# Dist_2_0.net
KiCad netlist of a schematic drawn in EAGLE
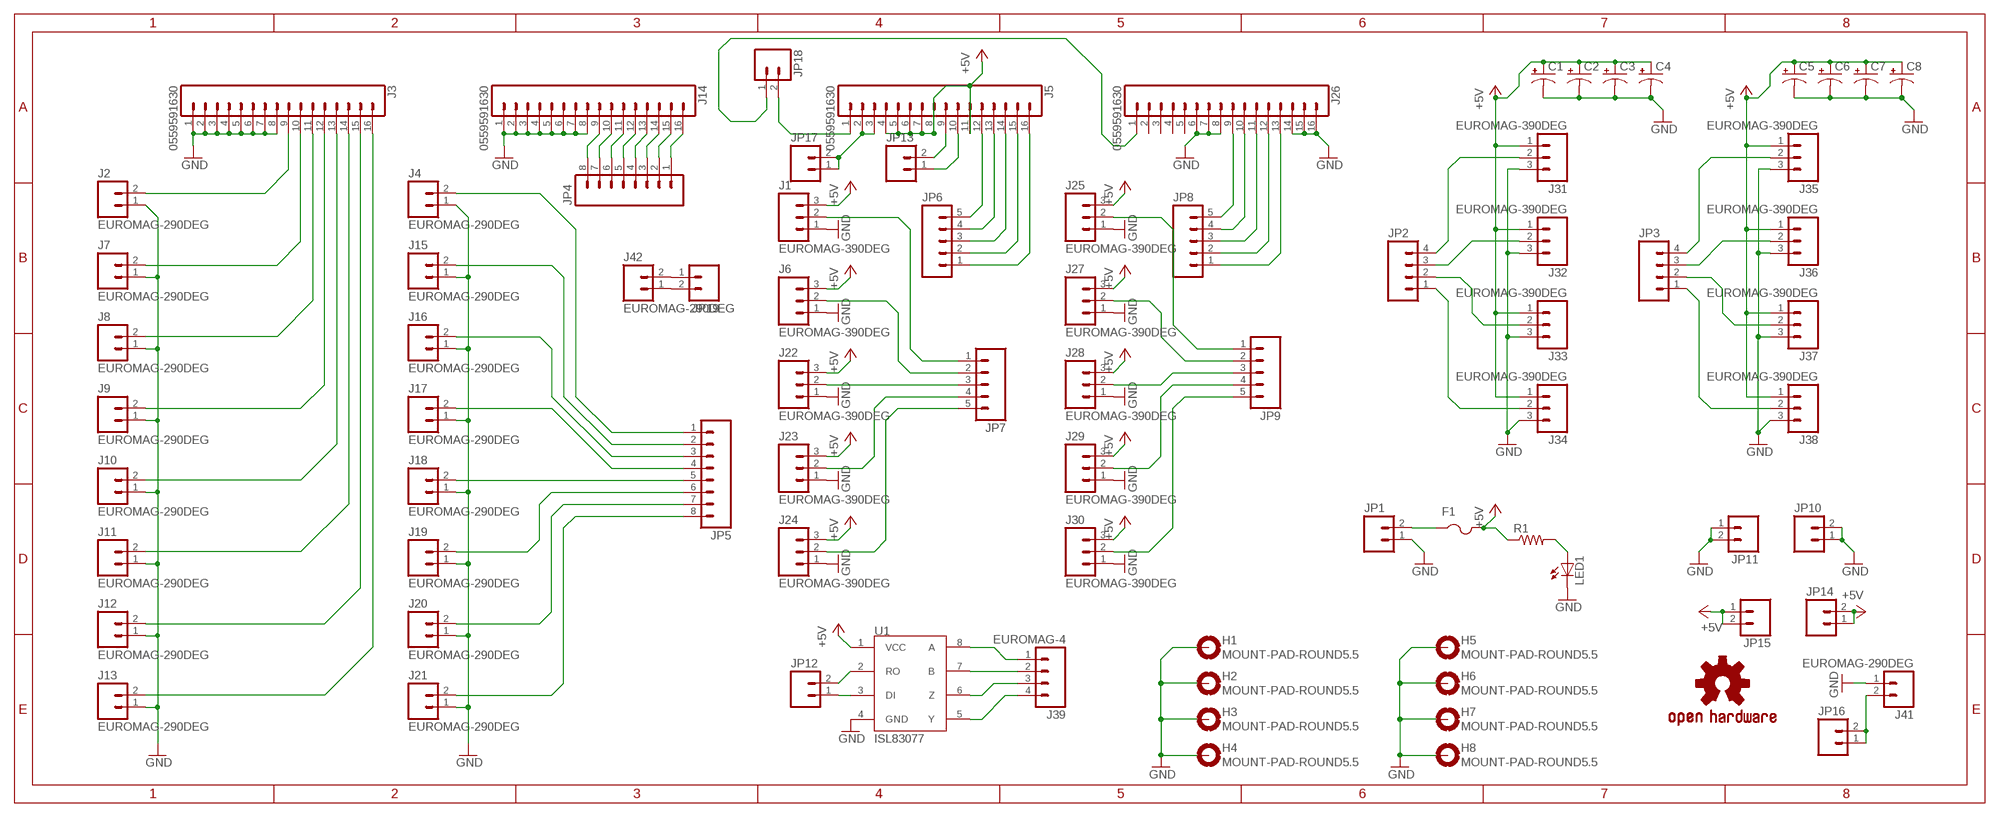
[diagram p0: schematic, sheet 1]

(export (version "E")
  (design (tool "Eeschema 10.0.6"))
  (components
    (comp (ref "C1")
      (value "CAP_POL3528")
      (footprint "eagle-import:EIA3528")
      (libsource (lib "eagle-import") (part "CAP_POL3528"))
    )
    (comp (ref "C2")
      (value "CAP_POL3528")
      (footprint "eagle-import:EIA3528")
      (libsource (lib "eagle-import") (part "CAP_POL3528"))
    )
    (comp (ref "C3")
      (value "CAP_POL3528")
      (footprint "eagle-import:EIA3528")
      (libsource (lib "eagle-import") (part "CAP_POL3528"))
    )
    (comp (ref "C4")
      (value "CAP_POL3528")
      (footprint "eagle-import:EIA3528")
      (libsource (lib "eagle-import") (part "CAP_POL3528"))
    )
    (comp (ref "C5")
      (value "CAP_POL3528")
      (footprint "eagle-import:EIA3528")
      (libsource (lib "eagle-import") (part "CAP_POL3528"))
    )
    (comp (ref "C6")
      (value "CAP_POL3528")
      (footprint "eagle-import:EIA3528")
      (libsource (lib "eagle-import") (part "CAP_POL3528"))
    )
    (comp (ref "C7")
      (value "CAP_POL3528")
      (footprint "eagle-import:EIA3528")
      (libsource (lib "eagle-import") (part "CAP_POL3528"))
    )
    (comp (ref "C8")
      (value "CAP_POL3528")
      (footprint "eagle-import:EIA3528")
      (libsource (lib "eagle-import") (part "CAP_POL3528"))
    )
    (comp (ref "F1")
      (value "PTCFUSE-1812")
      (footprint "eagle-import:1812")
      (libsource (lib "eagle-import") (part "PTCFUSE-1812"))
    )
    (comp (ref "H1")
      (value "MOUNT-PAD-ROUND5.5")
      (footprint "eagle-import:5,5-PAD")
      (libsource (lib "eagle-import") (part "MOUNT-PAD-ROUND5.5"))
    )
    (comp (ref "H2")
      (value "MOUNT-PAD-ROUND5.5")
      (footprint "eagle-import:5,5-PAD")
      (libsource (lib "eagle-import") (part "MOUNT-PAD-ROUND5.5"))
    )
    (comp (ref "H3")
      (value "MOUNT-PAD-ROUND5.5")
      (footprint "eagle-import:5,5-PAD")
      (libsource (lib "eagle-import") (part "MOUNT-PAD-ROUND5.5"))
    )
    (comp (ref "H4")
      (value "MOUNT-PAD-ROUND5.5")
      (footprint "eagle-import:5,5-PAD")
      (libsource (lib "eagle-import") (part "MOUNT-PAD-ROUND5.5"))
    )
    (comp (ref "H5")
      (value "MOUNT-PAD-ROUND5.5")
      (footprint "eagle-import:5,5-PAD")
      (libsource (lib "eagle-import") (part "MOUNT-PAD-ROUND5.5"))
    )
    (comp (ref "H6")
      (value "MOUNT-PAD-ROUND5.5")
      (footprint "eagle-import:5,5-PAD")
      (libsource (lib "eagle-import") (part "MOUNT-PAD-ROUND5.5"))
    )
    (comp (ref "H7")
      (value "MOUNT-PAD-ROUND5.5")
      (footprint "eagle-import:5,5-PAD")
      (libsource (lib "eagle-import") (part "MOUNT-PAD-ROUND5.5"))
    )
    (comp (ref "H8")
      (value "MOUNT-PAD-ROUND5.5")
      (footprint "eagle-import:5,5-PAD")
      (libsource (lib "eagle-import") (part "MOUNT-PAD-ROUND5.5"))
    )
    (comp (ref "J1")
      (value "EUROMAG-390DEG")
      (footprint "eagle-import:M3")
      (libsource (lib "eagle-import") (part "EUROMAG-390DEG"))
    )
    (comp (ref "J2")
      (value "EUROMAG-290DEG")
      (footprint "eagle-import:M2")
      (libsource (lib "eagle-import") (part "EUROMAG-290DEG"))
    )
    (comp (ref "J3")
      (value "0559591630")
      (footprint "eagle-import:0559591630")
      (libsource (lib "eagle-import") (part "0559591630"))
    )
    (comp (ref "J4")
      (value "EUROMAG-290DEG")
      (footprint "eagle-import:M2")
      (libsource (lib "eagle-import") (part "EUROMAG-290DEG"))
    )
    (comp (ref "J5")
      (value "0559591630")
      (footprint "eagle-import:0559591630")
      (libsource (lib "eagle-import") (part "0559591630"))
    )
    (comp (ref "J6")
      (value "EUROMAG-390DEG")
      (footprint "eagle-import:M3")
      (libsource (lib "eagle-import") (part "EUROMAG-390DEG"))
    )
    (comp (ref "J7")
      (value "EUROMAG-290DEG")
      (footprint "eagle-import:M2")
      (libsource (lib "eagle-import") (part "EUROMAG-290DEG"))
    )
    (comp (ref "J8")
      (value "EUROMAG-290DEG")
      (footprint "eagle-import:M2")
      (libsource (lib "eagle-import") (part "EUROMAG-290DEG"))
    )
    (comp (ref "J9")
      (value "EUROMAG-290DEG")
      (footprint "eagle-import:M2")
      (libsource (lib "eagle-import") (part "EUROMAG-290DEG"))
    )
    (comp (ref "J10")
      (value "EUROMAG-290DEG")
      (footprint "eagle-import:M2")
      (libsource (lib "eagle-import") (part "EUROMAG-290DEG"))
    )
    (comp (ref "J11")
      (value "EUROMAG-290DEG")
      (footprint "eagle-import:M2")
      (libsource (lib "eagle-import") (part "EUROMAG-290DEG"))
    )
    (comp (ref "J12")
      (value "EUROMAG-290DEG")
      (footprint "eagle-import:M2")
      (libsource (lib "eagle-import") (part "EUROMAG-290DEG"))
    )
    (comp (ref "J13")
      (value "EUROMAG-290DEG")
      (footprint "eagle-import:M2")
      (libsource (lib "eagle-import") (part "EUROMAG-290DEG"))
    )
    (comp (ref "J14")
      (value "0559591630")
      (footprint "eagle-import:0559591630")
      (libsource (lib "eagle-import") (part "0559591630"))
    )
    (comp (ref "J15")
      (value "EUROMAG-290DEG")
      (footprint "eagle-import:M2")
      (libsource (lib "eagle-import") (part "EUROMAG-290DEG"))
    )
    (comp (ref "J16")
      (value "EUROMAG-290DEG")
      (footprint "eagle-import:M2")
      (libsource (lib "eagle-import") (part "EUROMAG-290DEG"))
    )
    (comp (ref "J17")
      (value "EUROMAG-290DEG")
      (footprint "eagle-import:M2")
      (libsource (lib "eagle-import") (part "EUROMAG-290DEG"))
    )
    (comp (ref "J18")
      (value "EUROMAG-290DEG")
      (footprint "eagle-import:M2")
      (libsource (lib "eagle-import") (part "EUROMAG-290DEG"))
    )
    (comp (ref "J19")
      (value "EUROMAG-290DEG")
      (footprint "eagle-import:M2")
      (libsource (lib "eagle-import") (part "EUROMAG-290DEG"))
    )
    (comp (ref "J20")
      (value "EUROMAG-290DEG")
      (footprint "eagle-import:M2")
      (libsource (lib "eagle-import") (part "EUROMAG-290DEG"))
    )
    (comp (ref "J21")
      (value "EUROMAG-290DEG")
      (footprint "eagle-import:M2")
      (libsource (lib "eagle-import") (part "EUROMAG-290DEG"))
    )
    (comp (ref "J22")
      (value "EUROMAG-390DEG")
      (footprint "eagle-import:M3")
      (libsource (lib "eagle-import") (part "EUROMAG-390DEG"))
    )
    (comp (ref "J23")
      (value "EUROMAG-390DEG")
      (footprint "eagle-import:M3")
      (libsource (lib "eagle-import") (part "EUROMAG-390DEG"))
    )
    (comp (ref "J24")
      (value "EUROMAG-390DEG")
      (footprint "eagle-import:M3")
      (libsource (lib "eagle-import") (part "EUROMAG-390DEG"))
    )
    (comp (ref "J25")
      (value "EUROMAG-390DEG")
      (footprint "eagle-import:M3")
      (libsource (lib "eagle-import") (part "EUROMAG-390DEG"))
    )
    (comp (ref "J26")
      (value "0559591630")
      (footprint "eagle-import:0559591630")
      (libsource (lib "eagle-import") (part "0559591630"))
    )
    (comp (ref "J27")
      (value "EUROMAG-390DEG")
      (footprint "eagle-import:M3")
      (libsource (lib "eagle-import") (part "EUROMAG-390DEG"))
    )
    (comp (ref "J28")
      (value "EUROMAG-390DEG")
      (footprint "eagle-import:M3")
      (libsource (lib "eagle-import") (part "EUROMAG-390DEG"))
    )
    (comp (ref "J29")
      (value "EUROMAG-390DEG")
      (footprint "eagle-import:M3")
      (libsource (lib "eagle-import") (part "EUROMAG-390DEG"))
    )
    (comp (ref "J30")
      (value "EUROMAG-390DEG")
      (footprint "eagle-import:M3")
      (libsource (lib "eagle-import") (part "EUROMAG-390DEG"))
    )
    (comp (ref "J31")
      (value "EUROMAG-390DEG")
      (footprint "eagle-import:M3")
      (libsource (lib "eagle-import") (part "EUROMAG-390DEG"))
    )
    (comp (ref "J32")
      (value "EUROMAG-390DEG")
      (footprint "eagle-import:M3")
      (libsource (lib "eagle-import") (part "EUROMAG-390DEG"))
    )
    (comp (ref "J33")
      (value "EUROMAG-390DEG")
      (footprint "eagle-import:M3")
      (libsource (lib "eagle-import") (part "EUROMAG-390DEG"))
    )
    (comp (ref "J34")
      (value "EUROMAG-390DEG")
      (footprint "eagle-import:M3")
      (libsource (lib "eagle-import") (part "EUROMAG-390DEG"))
    )
    (comp (ref "J35")
      (value "EUROMAG-390DEG")
      (footprint "eagle-import:M3")
      (libsource (lib "eagle-import") (part "EUROMAG-390DEG"))
    )
    (comp (ref "J36")
      (value "EUROMAG-390DEG")
      (footprint "eagle-import:M3")
      (libsource (lib "eagle-import") (part "EUROMAG-390DEG"))
    )
    (comp (ref "J37")
      (value "EUROMAG-390DEG")
      (footprint "eagle-import:M3")
      (libsource (lib "eagle-import") (part "EUROMAG-390DEG"))
    )
    (comp (ref "J38")
      (value "EUROMAG-390DEG")
      (footprint "eagle-import:M3")
      (libsource (lib "eagle-import") (part "EUROMAG-390DEG"))
    )
    (comp (ref "J39")
      (value "EUROMAG-4")
      (footprint "eagle-import:M4")
      (libsource (lib "eagle-import") (part "EUROMAG-4"))
    )
    (comp (ref "J41")
      (value "EUROMAG-290DEG")
      (footprint "eagle-import:M2")
      (libsource (lib "eagle-import") (part "EUROMAG-290DEG"))
    )
    (comp (ref "J42")
      (value "EUROMAG-290DEG")
      (footprint "eagle-import:M2")
      (libsource (lib "eagle-import") (part "EUROMAG-290DEG"))
    )
    (comp (ref "JP1")
      (value "M02POLAR_LOCK")
      (footprint "eagle-import:MOLEX-1X2_LOCK")
      (libsource (lib "eagle-import") (part "M02POLAR_LOCK"))
    )
    (comp (ref "JP2")
      (value "M04POLAR_LOCK")
      (footprint "eagle-import:MOLEX-1X4_LOCK")
      (libsource (lib "eagle-import") (part "M04POLAR_LOCK"))
    )
    (comp (ref "JP3")
      (value "M04POLAR_LOCK")
      (footprint "eagle-import:MOLEX-1X4_LOCK")
      (libsource (lib "eagle-import") (part "M04POLAR_LOCK"))
    )
    (comp (ref "JP4")
      (value "M08LOCK_LONGPADS")
      (footprint "eagle-import:1X08_LOCK_LONGPADS")
      (libsource (lib "eagle-import") (part "M08LOCK_LONGPADS"))
    )
    (comp (ref "JP5")
      (value "M08LOCK_LONGPADS")
      (footprint "eagle-import:1X08_LOCK_LONGPADS")
      (libsource (lib "eagle-import") (part "M08LOCK_LONGPADS"))
    )
    (comp (ref "JP6")
      (value "M05LOCK_LONGPADS")
      (footprint "eagle-import:1X05_LOCK_LONGPADS")
      (libsource (lib "eagle-import") (part "M05LOCK_LONGPADS"))
    )
    (comp (ref "JP7")
      (value "M05LOCK_LONGPADS")
      (footprint "eagle-import:1X05_LOCK_LONGPADS")
      (libsource (lib "eagle-import") (part "M05LOCK_LONGPADS"))
    )
    (comp (ref "JP8")
      (value "M05LOCK_LONGPADS")
      (footprint "eagle-import:1X05_LOCK_LONGPADS")
      (libsource (lib "eagle-import") (part "M05LOCK_LONGPADS"))
    )
    (comp (ref "JP9")
      (value "M05LOCK_LONGPADS")
      (footprint "eagle-import:1X05_LOCK_LONGPADS")
      (libsource (lib "eagle-import") (part "M05LOCK_LONGPADS"))
    )
    (comp (ref "JP10")
      (value "M02PTH")
      (footprint "eagle-import:1X02")
      (libsource (lib "eagle-import") (part "SparkFun-Connectors_M02PTH"))
    )
    (comp (ref "JP11")
      (value "M02PTH")
      (footprint "eagle-import:1X02")
      (libsource (lib "eagle-import") (part "SparkFun-Connectors_M02PTH"))
    )
    (comp (ref "JP12")
      (value "M02PTH")
      (footprint "eagle-import:1X02")
      (libsource (lib "eagle-import") (part "SparkFun-Connectors_M02PTH"))
    )
    (comp (ref "JP13")
      (value "M02PTH")
      (footprint "eagle-import:1X02")
      (libsource (lib "eagle-import") (part "SparkFun-Connectors_M02PTH"))
    )
    (comp (ref "JP14")
      (value "M02PTH")
      (footprint "eagle-import:1X02")
      (libsource (lib "eagle-import") (part "SparkFun-Connectors_M02PTH"))
    )
    (comp (ref "JP15")
      (value "M02PTH")
      (footprint "eagle-import:1X02")
      (libsource (lib "eagle-import") (part "SparkFun-Connectors_M02PTH"))
    )
    (comp (ref "JP16")
      (value "M02PTH")
      (footprint "eagle-import:1X02")
      (libsource (lib "eagle-import") (part "SparkFun-Connectors_M02PTH"))
    )
    (comp (ref "JP17")
      (value "M02PTH")
      (footprint "eagle-import:1X02")
      (libsource (lib "eagle-import") (part "SparkFun-Connectors_M02PTH"))
    )
    (comp (ref "JP18")
      (value "M02PTH")
      (footprint "eagle-import:1X02")
      (libsource (lib "eagle-import") (part "SparkFun-Connectors_M02PTH"))
    )
    (comp (ref "JP19")
      (value "M02PTH")
      (footprint "eagle-import:1X02")
      (libsource (lib "eagle-import") (part "SparkFun-Connectors_M02PTH"))
    )
    (comp (ref "LED1")
      (value "LEDCHIPLED_0805")
      (footprint "eagle-import:CHIPLED_0805")
      (libsource (lib "eagle-import") (part "LEDCHIPLED_0805"))
    )
    (comp (ref "R1")
      (value "R-US_R0805")
      (footprint "eagle-import:R0805")
      (libsource (lib "eagle-import") (part "R-US_R0805"))
    )
    (comp (ref "U$1")
      (value "OSHW-LOGOL")
      (footprint "eagle-import:OSHW-LOGO-L")
      (libsource (lib "eagle-import") (part "OSHW-LOGOL"))
    )
    (comp (ref "U1")
      (value "ISL83077")
      (footprint "eagle-import:SO08")
      (libsource (lib "eagle-import") (part "ISL83077"))
    )
  )
  (nets
    (net (code "1") (name "+5V") (class "Default")
      (node (ref "C1") (pin "A") (pinfunction "+_A") (pintype "passive"))
      (node (ref "C2") (pin "A") (pinfunction "+_A") (pintype "passive"))
      (node (ref "C3") (pin "A") (pinfunction "+_A") (pintype "passive"))
      (node (ref "C4") (pin "A") (pinfunction "+_A") (pintype "passive"))
      (node (ref "C5") (pin "A") (pinfunction "+_A") (pintype "passive"))
      (node (ref "C6") (pin "A") (pinfunction "+_A") (pintype "passive"))
      (node (ref "C7") (pin "A") (pinfunction "+_A") (pintype "passive"))
      (node (ref "C8") (pin "A") (pinfunction "+_A") (pintype "passive"))
      (node (ref "F1") (pin "2") (pinfunction "2_2") (pintype "passive"))
      (node (ref "J1") (pin "3") (pinfunction "3_3") (pintype "passive"))
      (node (ref "J22") (pin "3") (pinfunction "3_3") (pintype "passive"))
      (node (ref "J23") (pin "3") (pinfunction "3_3") (pintype "passive"))
      (node (ref "J24") (pin "3") (pinfunction "3_3") (pintype "passive"))
      (node (ref "J25") (pin "3") (pinfunction "3_3") (pintype "passive"))
      (node (ref "J27") (pin "3") (pinfunction "3_3") (pintype "passive"))
      (node (ref "J28") (pin "3") (pinfunction "3_3") (pintype "passive"))
      (node (ref "J29") (pin "3") (pinfunction "3_3") (pintype "passive"))
      (node (ref "J30") (pin "3") (pinfunction "3_3") (pintype "passive"))
      (node (ref "J31") (pin "1") (pinfunction "1_1") (pintype "passive"))
      (node (ref "J32") (pin "1") (pinfunction "1_1") (pintype "passive"))
      (node (ref "J33") (pin "1") (pinfunction "1_1") (pintype "passive"))
      (node (ref "J34") (pin "1") (pinfunction "1_1") (pintype "passive"))
      (node (ref "J35") (pin "1") (pinfunction "1_1") (pintype "passive"))
      (node (ref "J36") (pin "1") (pinfunction "1_1") (pintype "passive"))
      (node (ref "J37") (pin "1") (pinfunction "1_1") (pintype "passive"))
      (node (ref "J38") (pin "1") (pinfunction "1_1") (pintype "passive"))
      (node (ref "J5") (pin "11") (pinfunction "11_11") (pintype "passive"))
      (node (ref "J5") (pin "4") (pinfunction "4_4") (pintype "passive"))
      (node (ref "J5") (pin "5") (pinfunction "5_5") (pintype "passive"))
      (node (ref "J5") (pin "6") (pinfunction "6_6") (pintype "passive"))
      (node (ref "J5") (pin "7") (pinfunction "7_7") (pintype "passive"))
      (node (ref "J5") (pin "8") (pinfunction "8_8") (pintype "passive"))
      (node (ref "J6") (pin "3") (pinfunction "3_3") (pintype "passive"))
      (node (ref "JP14") (pin "1") (pinfunction "1_1") (pintype "passive"))
      (node (ref "JP14") (pin "2") (pinfunction "2_2") (pintype "passive"))
      (node (ref "JP15") (pin "1") (pinfunction "1_1") (pintype "passive"))
      (node (ref "JP15") (pin "2") (pinfunction "2_2") (pintype "passive"))
      (node (ref "R1") (pin "1") (pinfunction "1_1") (pintype "passive"))
      (node (ref "U1") (pin "1") (pinfunction "VCC_1") (pintype "bidirectional"))
    )
    (net (code "2") (name "GND") (class "Default")
      (node (ref "C1") (pin "C") (pinfunction "-_C") (pintype "passive"))
      (node (ref "C2") (pin "C") (pinfunction "-_C") (pintype "passive"))
      (node (ref "C3") (pin "C") (pinfunction "-_C") (pintype "passive"))
      (node (ref "C4") (pin "C") (pinfunction "-_C") (pintype "passive"))
      (node (ref "C5") (pin "C") (pinfunction "-_C") (pintype "passive"))
      (node (ref "C6") (pin "C") (pinfunction "-_C") (pintype "passive"))
      (node (ref "C7") (pin "C") (pinfunction "-_C") (pintype "passive"))
      (node (ref "C8") (pin "C") (pinfunction "-_C") (pintype "passive"))
      (node (ref "H1") (pin "B5,5") (pinfunction "MOUNT_B5,5") (pintype "passive"))
      (node (ref "H2") (pin "B5,5") (pinfunction "MOUNT_B5,5") (pintype "passive"))
      (node (ref "H3") (pin "B5,5") (pinfunction "MOUNT_B5,5") (pintype "passive"))
      (node (ref "H4") (pin "B5,5") (pinfunction "MOUNT_B5,5") (pintype "passive"))
      (node (ref "H5") (pin "B5,5") (pinfunction "MOUNT_B5,5") (pintype "passive"))
      (node (ref "H6") (pin "B5,5") (pinfunction "MOUNT_B5,5") (pintype "passive"))
      (node (ref "H7") (pin "B5,5") (pinfunction "MOUNT_B5,5") (pintype "passive"))
      (node (ref "H8") (pin "B5,5") (pinfunction "MOUNT_B5,5") (pintype "passive"))
      (node (ref "J1") (pin "1") (pinfunction "1_1") (pintype "passive"))
      (node (ref "J10") (pin "1") (pinfunction "1_1") (pintype "passive"))
      (node (ref "J11") (pin "1") (pinfunction "1_1") (pintype "passive"))
      (node (ref "J12") (pin "1") (pinfunction "1_1") (pintype "passive"))
      (node (ref "J13") (pin "1") (pinfunction "1_1") (pintype "passive"))
      (node (ref "J14") (pin "1") (pinfunction "1_1") (pintype "passive"))
      (node (ref "J14") (pin "2") (pinfunction "2_2") (pintype "passive"))
      (node (ref "J14") (pin "3") (pinfunction "3_3") (pintype "passive"))
      (node (ref "J14") (pin "4") (pinfunction "4_4") (pintype "passive"))
      (node (ref "J14") (pin "5") (pinfunction "5_5") (pintype "passive"))
      (node (ref "J14") (pin "6") (pinfunction "6_6") (pintype "passive"))
      (node (ref "J14") (pin "7") (pinfunction "7_7") (pintype "passive"))
      (node (ref "J14") (pin "8") (pinfunction "8_8") (pintype "passive"))
      (node (ref "J15") (pin "1") (pinfunction "1_1") (pintype "passive"))
      (node (ref "J16") (pin "1") (pinfunction "1_1") (pintype "passive"))
      (node (ref "J17") (pin "1") (pinfunction "1_1") (pintype "passive"))
      (node (ref "J18") (pin "1") (pinfunction "1_1") (pintype "passive"))
      (node (ref "J19") (pin "1") (pinfunction "1_1") (pintype "passive"))
      (node (ref "J2") (pin "1") (pinfunction "1_1") (pintype "passive"))
      (node (ref "J20") (pin "1") (pinfunction "1_1") (pintype "passive"))
      (node (ref "J21") (pin "1") (pinfunction "1_1") (pintype "passive"))
      (node (ref "J22") (pin "1") (pinfunction "1_1") (pintype "passive"))
      (node (ref "J23") (pin "1") (pinfunction "1_1") (pintype "passive"))
      (node (ref "J24") (pin "1") (pinfunction "1_1") (pintype "passive"))
      (node (ref "J25") (pin "1") (pinfunction "1_1") (pintype "passive"))
      (node (ref "J26") (pin "14") (pinfunction "14_14") (pintype "passive"))
      (node (ref "J26") (pin "15") (pinfunction "15_15") (pintype "passive"))
      (node (ref "J26") (pin "16") (pinfunction "16_16") (pintype "passive"))
      (node (ref "J26") (pin "6") (pinfunction "6_6") (pintype "passive"))
      (node (ref "J26") (pin "7") (pinfunction "7_7") (pintype "passive"))
      (node (ref "J26") (pin "8") (pinfunction "8_8") (pintype "passive"))
      (node (ref "J27") (pin "1") (pinfunction "1_1") (pintype "passive"))
      (node (ref "J28") (pin "1") (pinfunction "1_1") (pintype "passive"))
      (node (ref "J29") (pin "1") (pinfunction "1_1") (pintype "passive"))
      (node (ref "J3") (pin "1") (pinfunction "1_1") (pintype "passive"))
      (node (ref "J3") (pin "2") (pinfunction "2_2") (pintype "passive"))
      (node (ref "J3") (pin "3") (pinfunction "3_3") (pintype "passive"))
      (node (ref "J3") (pin "4") (pinfunction "4_4") (pintype "passive"))
      (node (ref "J3") (pin "5") (pinfunction "5_5") (pintype "passive"))
      (node (ref "J3") (pin "6") (pinfunction "6_6") (pintype "passive"))
      (node (ref "J3") (pin "7") (pinfunction "7_7") (pintype "passive"))
      (node (ref "J3") (pin "8") (pinfunction "8_8") (pintype "passive"))
      (node (ref "J30") (pin "1") (pinfunction "1_1") (pintype "passive"))
      (node (ref "J31") (pin "3") (pinfunction "3_3") (pintype "passive"))
      (node (ref "J32") (pin "3") (pinfunction "3_3") (pintype "passive"))
      (node (ref "J33") (pin "3") (pinfunction "3_3") (pintype "passive"))
      (node (ref "J34") (pin "3") (pinfunction "3_3") (pintype "passive"))
      (node (ref "J35") (pin "3") (pinfunction "3_3") (pintype "passive"))
      (node (ref "J36") (pin "3") (pinfunction "3_3") (pintype "passive"))
      (node (ref "J37") (pin "3") (pinfunction "3_3") (pintype "passive"))
      (node (ref "J38") (pin "3") (pinfunction "3_3") (pintype "passive"))
      (node (ref "J4") (pin "1") (pinfunction "1_1") (pintype "passive"))
      (node (ref "J41") (pin "1") (pinfunction "1_1") (pintype "passive"))
      (node (ref "J6") (pin "1") (pinfunction "1_1") (pintype "passive"))
      (node (ref "J7") (pin "1") (pinfunction "1_1") (pintype "passive"))
      (node (ref "J8") (pin "1") (pinfunction "1_1") (pintype "passive"))
      (node (ref "J9") (pin "1") (pinfunction "1_1") (pintype "passive"))
      (node (ref "JP1") (pin "1") (pinfunction "1_1") (pintype "passive"))
      (node (ref "JP10") (pin "1") (pinfunction "1_1") (pintype "passive"))
      (node (ref "JP10") (pin "2") (pinfunction "2_2") (pintype "passive"))
      (node (ref "JP11") (pin "1") (pinfunction "1_1") (pintype "passive"))
      (node (ref "JP11") (pin "2") (pinfunction "2_2") (pintype "passive"))
      (node (ref "LED1") (pin "C") (pinfunction "C_C") (pintype "passive"))
      (node (ref "U1") (pin "4") (pinfunction "GND_4") (pintype "bidirectional"))
    )
    (net (code "3") (name "Net-(F1-Pad1)") (class "Default")
      (node (ref "F1") (pin "1") (pinfunction "1_1") (pintype "passive"))
      (node (ref "JP1") (pin "2") (pinfunction "2_2") (pintype "passive"))
    )
    (net (code "4") (name "Net-(J1-Pad2)") (class "Default")
      (node (ref "J1") (pin "2") (pinfunction "2_2") (pintype "passive"))
      (node (ref "JP7") (pin "1") (pinfunction "1_1") (pintype "passive"))
    )
    (net (code "5") (name "Net-(J2-Pad2)") (class "Default")
      (node (ref "J2") (pin "2") (pinfunction "2_2") (pintype "passive"))
      (node (ref "J3") (pin "9") (pinfunction "9_9") (pintype "passive"))
    )
    (net (code "6") (name "Net-(J3-Pad10)") (class "Default")
      (node (ref "J3") (pin "10") (pinfunction "10_10") (pintype "passive"))
      (node (ref "J7") (pin "2") (pinfunction "2_2") (pintype "passive"))
    )
    (net (code "7") (name "Net-(J3-Pad11)") (class "Default")
      (node (ref "J3") (pin "11") (pinfunction "11_11") (pintype "passive"))
      (node (ref "J8") (pin "2") (pinfunction "2_2") (pintype "passive"))
    )
    (net (code "8") (name "Net-(J3-Pad12)") (class "Default")
      (node (ref "J3") (pin "12") (pinfunction "12_12") (pintype "passive"))
      (node (ref "J9") (pin "2") (pinfunction "2_2") (pintype "passive"))
    )
    (net (code "9") (name "Net-(J4-Pad2)") (class "Default")
      (node (ref "J4") (pin "2") (pinfunction "2_2") (pintype "passive"))
      (node (ref "JP5") (pin "1") (pinfunction "1_1") (pintype "passive"))
    )
    (net (code "10") (name "Net-(J5-Pad1)") (class "Default")
      (node (ref "J5") (pin "1") (pinfunction "1_1") (pintype "passive"))
      (node (ref "JP18") (pin "2") (pinfunction "2_2") (pintype "passive"))
    )
    (net (code "11") (name "Net-(J5-Pad2)") (class "Default")
      (node (ref "J5") (pin "2") (pinfunction "2_2") (pintype "passive"))
      (node (ref "J5") (pin "3") (pinfunction "3_3") (pintype "passive"))
      (node (ref "JP17") (pin "1") (pinfunction "1_1") (pintype "passive"))
      (node (ref "JP17") (pin "2") (pinfunction "2_2") (pintype "passive"))
    )
    (net (code "12") (name "Net-(J5-Pad9)") (class "Default")
      (node (ref "J5") (pin "9") (pinfunction "9_9") (pintype "passive"))
      (node (ref "JP13") (pin "2") (pinfunction "2_2") (pintype "passive"))
    )
    (net (code "13") (name "Net-(J5-Pad10)") (class "Default")
      (node (ref "J5") (pin "10") (pinfunction "10_10") (pintype "passive"))
      (node (ref "JP13") (pin "1") (pinfunction "1_1") (pintype "passive"))
    )
    (net (code "14") (name "Net-(J5-Pad12)") (class "Default")
      (node (ref "J5") (pin "12") (pinfunction "12_12") (pintype "passive"))
      (node (ref "JP6") (pin "5") (pinfunction "5_5") (pintype "passive"))
    )
    (net (code "15") (name "Net-(J5-Pad13)") (class "Default")
      (node (ref "J5") (pin "13") (pinfunction "13_13") (pintype "passive"))
      (node (ref "JP6") (pin "4") (pinfunction "4_4") (pintype "passive"))
    )
    (net (code "16") (name "Net-(J5-Pad14)") (class "Default")
      (node (ref "J5") (pin "14") (pinfunction "14_14") (pintype "passive"))
      (node (ref "JP6") (pin "3") (pinfunction "3_3") (pintype "passive"))
    )
    (net (code "17") (name "Net-(J5-Pad15)") (class "Default")
      (node (ref "J5") (pin "15") (pinfunction "15_15") (pintype "passive"))
      (node (ref "JP6") (pin "2") (pinfunction "2_2") (pintype "passive"))
    )
    (net (code "18") (name "Net-(J5-Pad16)") (class "Default")
      (node (ref "J5") (pin "16") (pinfunction "16_16") (pintype "passive"))
      (node (ref "JP6") (pin "1") (pinfunction "1_1") (pintype "passive"))
    )
    (net (code "19") (name "Net-(J6-Pad2)") (class "Default")
      (node (ref "J6") (pin "2") (pinfunction "2_2") (pintype "passive"))
      (node (ref "JP7") (pin "2") (pinfunction "2_2") (pintype "passive"))
    )
    (net (code "20") (name "Net-(J10-Pad2)") (class "Default")
      (node (ref "J10") (pin "2") (pinfunction "2_2") (pintype "passive"))
      (node (ref "J3") (pin "13") (pinfunction "13_13") (pintype "passive"))
    )
    (net (code "21") (name "Net-(J11-Pad2)") (class "Default")
      (node (ref "J11") (pin "2") (pinfunction "2_2") (pintype "passive"))
      (node (ref "J3") (pin "14") (pinfunction "14_14") (pintype "passive"))
    )
    (net (code "22") (name "Net-(J12-Pad2)") (class "Default")
      (node (ref "J12") (pin "2") (pinfunction "2_2") (pintype "passive"))
      (node (ref "J3") (pin "15") (pinfunction "15_15") (pintype "passive"))
    )
    (net (code "23") (name "Net-(J13-Pad2)") (class "Default")
      (node (ref "J13") (pin "2") (pinfunction "2_2") (pintype "passive"))
      (node (ref "J3") (pin "16") (pinfunction "16_16") (pintype "passive"))
    )
    (net (code "24") (name "Net-(J14-Pad9)") (class "Default")
      (node (ref "J14") (pin "9") (pinfunction "9_9") (pintype "passive"))
      (node (ref "JP4") (pin "8") (pinfunction "8_8") (pintype "passive"))
    )
    (net (code "25") (name "Net-(J14-Pad10)") (class "Default")
      (node (ref "J14") (pin "10") (pinfunction "10_10") (pintype "passive"))
      (node (ref "JP4") (pin "7") (pinfunction "7_7") (pintype "passive"))
    )
    (net (code "26") (name "Net-(J14-Pad11)") (class "Default")
      (node (ref "J14") (pin "11") (pinfunction "11_11") (pintype "passive"))
      (node (ref "JP4") (pin "6") (pinfunction "6_6") (pintype "passive"))
    )
    (net (code "27") (name "Net-(J14-Pad12)") (class "Default")
      (node (ref "J14") (pin "12") (pinfunction "12_12") (pintype "passive"))
      (node (ref "JP4") (pin "5") (pinfunction "5_5") (pintype "passive"))
    )
    (net (code "28") (name "Net-(J14-Pad13)") (class "Default")
      (node (ref "J14") (pin "13") (pinfunction "13_13") (pintype "passive"))
      (node (ref "JP4") (pin "4") (pinfunction "4_4") (pintype "passive"))
    )
    (net (code "29") (name "Net-(J14-Pad14)") (class "Default")
      (node (ref "J14") (pin "14") (pinfunction "14_14") (pintype "passive"))
      (node (ref "JP4") (pin "3") (pinfunction "3_3") (pintype "passive"))
    )
    (net (code "30") (name "Net-(J14-Pad15)") (class "Default")
      (node (ref "J14") (pin "15") (pinfunction "15_15") (pintype "passive"))
      (node (ref "JP4") (pin "2") (pinfunction "2_2") (pintype "passive"))
    )
    (net (code "31") (name "Net-(J14-Pad16)") (class "Default")
      (node (ref "J14") (pin "16") (pinfunction "16_16") (pintype "passive"))
      (node (ref "JP4") (pin "1") (pinfunction "1_1") (pintype "passive"))
    )
    (net (code "32") (name "Net-(J15-Pad2)") (class "Default")
      (node (ref "J15") (pin "2") (pinfunction "2_2") (pintype "passive"))
      (node (ref "JP5") (pin "2") (pinfunction "2_2") (pintype "passive"))
    )
    (net (code "33") (name "Net-(J16-Pad2)") (class "Default")
      (node (ref "J16") (pin "2") (pinfunction "2_2") (pintype "passive"))
      (node (ref "JP5") (pin "3") (pinfunction "3_3") (pintype "passive"))
    )
    (net (code "34") (name "Net-(J17-Pad2)") (class "Default")
      (node (ref "J17") (pin "2") (pinfunction "2_2") (pintype "passive"))
      (node (ref "JP5") (pin "4") (pinfunction "4_4") (pintype "passive"))
    )
    (net (code "35") (name "Net-(J18-Pad2)") (class "Default")
      (node (ref "J18") (pin "2") (pinfunction "2_2") (pintype "passive"))
      (node (ref "JP5") (pin "5") (pinfunction "5_5") (pintype "passive"))
    )
    (net (code "36") (name "Net-(J19-Pad2)") (class "Default")
      (node (ref "J19") (pin "2") (pinfunction "2_2") (pintype "passive"))
      (node (ref "JP5") (pin "6") (pinfunction "6_6") (pintype "passive"))
    )
    (net (code "37") (name "Net-(J20-Pad2)") (class "Default")
      (node (ref "J20") (pin "2") (pinfunction "2_2") (pintype "passive"))
      (node (ref "JP5") (pin "7") (pinfunction "7_7") (pintype "passive"))
    )
    (net (code "38") (name "Net-(J21-Pad2)") (class "Default")
      (node (ref "J21") (pin "2") (pinfunction "2_2") (pintype "passive"))
      (node (ref "JP5") (pin "8") (pinfunction "8_8") (pintype "passive"))
    )
    (net (code "39") (name "Net-(J22-Pad2)") (class "Default")
      (node (ref "J22") (pin "2") (pinfunction "2_2") (pintype "passive"))
      (node (ref "JP7") (pin "3") (pinfunction "3_3") (pintype "passive"))
    )
    (net (code "40") (name "Net-(J23-Pad2)") (class "Default")
      (node (ref "J23") (pin "2") (pinfunction "2_2") (pintype "passive"))
      (node (ref "JP7") (pin "4") (pinfunction "4_4") (pintype "passive"))
    )
    (net (code "41") (name "Net-(J24-Pad2)") (class "Default")
      (node (ref "J24") (pin "2") (pinfunction "2_2") (pintype "passive"))
      (node (ref "JP7") (pin "5") (pinfunction "5_5") (pintype "passive"))
    )
    (net (code "42") (name "Net-(J25-Pad2)") (class "Default")
      (node (ref "J25") (pin "2") (pinfunction "2_2") (pintype "passive"))
      (node (ref "JP9") (pin "1") (pinfunction "1_1") (pintype "passive"))
    )
    (net (code "43") (name "Net-(J26-Pad1)") (class "Default")
      (node (ref "J26") (pin "1") (pinfunction "1_1") (pintype "passive"))
      (node (ref "JP18") (pin "1") (pinfunction "1_1") (pintype "passive"))
    )
    (net (code "44") (name "Net-(J26-Pad9)") (class "Default")
      (node (ref "J26") (pin "9") (pinfunction "9_9") (pintype "passive"))
      (node (ref "JP8") (pin "5") (pinfunction "5_5") (pintype "passive"))
    )
    (net (code "45") (name "Net-(J26-Pad10)") (class "Default")
      (node (ref "J26") (pin "10") (pinfunction "10_10") (pintype "passive"))
      (node (ref "JP8") (pin "4") (pinfunction "4_4") (pintype "passive"))
    )
    (net (code "46") (name "Net-(J26-Pad11)") (class "Default")
      (node (ref "J26") (pin "11") (pinfunction "11_11") (pintype "passive"))
      (node (ref "JP8") (pin "3") (pinfunction "3_3") (pintype "passive"))
    )
    (net (code "47") (name "Net-(J26-Pad12)") (class "Default")
      (node (ref "J26") (pin "12") (pinfunction "12_12") (pintype "passive"))
      (node (ref "JP8") (pin "2") (pinfunction "2_2") (pintype "passive"))
    )
    (net (code "48") (name "Net-(J26-Pad13)") (class "Default")
      (node (ref "J26") (pin "13") (pinfunction "13_13") (pintype "passive"))
      (node (ref "JP8") (pin "1") (pinfunction "1_1") (pintype "passive"))
    )
    (net (code "49") (name "Net-(J27-Pad2)") (class "Default")
      (node (ref "J27") (pin "2") (pinfunction "2_2") (pintype "passive"))
      (node (ref "JP9") (pin "2") (pinfunction "2_2") (pintype "passive"))
    )
    (net (code "50") (name "Net-(J28-Pad2)") (class "Default")
      (node (ref "J28") (pin "2") (pinfunction "2_2") (pintype "passive"))
      (node (ref "JP9") (pin "3") (pinfunction "3_3") (pintype "passive"))
    )
    (net (code "51") (name "Net-(J29-Pad2)") (class "Default")
      (node (ref "J29") (pin "2") (pinfunction "2_2") (pintype "passive"))
      (node (ref "JP9") (pin "4") (pinfunction "4_4") (pintype "passive"))
    )
    (net (code "52") (name "Net-(J30-Pad2)") (class "Default")
      (node (ref "J30") (pin "2") (pinfunction "2_2") (pintype "passive"))
      (node (ref "JP9") (pin "5") (pinfunction "5_5") (pintype "passive"))
    )
    (net (code "53") (name "Net-(J31-Pad2)") (class "Default")
      (node (ref "J31") (pin "2") (pinfunction "2_2") (pintype "passive"))
      (node (ref "JP2") (pin "4") (pinfunction "4_4") (pintype "passive"))
    )
    (net (code "54") (name "Net-(J32-Pad2)") (class "Default")
      (node (ref "J32") (pin "2") (pinfunction "2_2") (pintype "passive"))
      (node (ref "JP2") (pin "3") (pinfunction "3_3") (pintype "passive"))
    )
    (net (code "55") (name "Net-(J33-Pad2)") (class "Default")
      (node (ref "J33") (pin "2") (pinfunction "2_2") (pintype "passive"))
      (node (ref "JP2") (pin "2") (pinfunction "2_2") (pintype "passive"))
    )
    (net (code "56") (name "Net-(J34-Pad2)") (class "Default")
      (node (ref "J34") (pin "2") (pinfunction "2_2") (pintype "passive"))
      (node (ref "JP2") (pin "1") (pinfunction "1_1") (pintype "passive"))
    )
    (net (code "57") (name "Net-(J35-Pad2)") (class "Default")
      (node (ref "J35") (pin "2") (pinfunction "2_2") (pintype "passive"))
      (node (ref "JP3") (pin "4") (pinfunction "4_4") (pintype "passive"))
    )
    (net (code "58") (name "Net-(J36-Pad2)") (class "Default")
      (node (ref "J36") (pin "2") (pinfunction "2_2") (pintype "passive"))
      (node (ref "JP3") (pin "3") (pinfunction "3_3") (pintype "passive"))
    )
    (net (code "59") (name "Net-(J37-Pad2)") (class "Default")
      (node (ref "J37") (pin "2") (pinfunction "2_2") (pintype "passive"))
      (node (ref "JP3") (pin "2") (pinfunction "2_2") (pintype "passive"))
    )
    (net (code "60") (name "Net-(J38-Pad2)") (class "Default")
      (node (ref "J38") (pin "2") (pinfunction "2_2") (pintype "passive"))
      (node (ref "JP3") (pin "1") (pinfunction "1_1") (pintype "passive"))
    )
    (net (code "61") (name "Net-(J41-Pad2)") (class "Default")
      (node (ref "J41") (pin "2") (pinfunction "2_2") (pintype "passive"))
      (node (ref "JP16") (pin "1") (pinfunction "1_1") (pintype "passive"))
      (node (ref "JP16") (pin "2") (pinfunction "2_2") (pintype "passive"))
    )
    (net (code "62") (name "Net-(J42-Pad1)") (class "Default")
      (node (ref "J42") (pin "1") (pinfunction "1_1") (pintype "passive"))
      (node (ref "JP19") (pin "2") (pinfunction "2_2") (pintype "passive"))
    )
    (net (code "63") (name "Net-(J42-Pad2)") (class "Default")
      (node (ref "J42") (pin "2") (pinfunction "2_2") (pintype "passive"))
      (node (ref "JP19") (pin "1") (pinfunction "1_1") (pintype "passive"))
    )
    (net (code "64") (name "Net-(LED1-PadA)") (class "Default")
      (node (ref "LED1") (pin "A") (pinfunction "A_A") (pintype "passive"))
      (node (ref "R1") (pin "2") (pinfunction "2_2") (pintype "passive"))
    )
    (net (code "65") (name "Net-(U1-A)") (class "Default")
      (node (ref "J39") (pin "1") (pinfunction "1_1") (pintype "passive"))
      (node (ref "U1") (pin "8") (pinfunction "A_8") (pintype "bidirectional"))
    )
    (net (code "66") (name "Net-(U1-B)") (class "Default")
      (node (ref "J39") (pin "2") (pinfunction "2_2") (pintype "passive"))
      (node (ref "U1") (pin "7") (pinfunction "B_7") (pintype "bidirectional"))
    )
    (net (code "67") (name "Net-(U1-DI)") (class "Default")
      (node (ref "JP12") (pin "1") (pinfunction "1_1") (pintype "passive"))
      (node (ref "U1") (pin "3") (pinfunction "DI_3") (pintype "bidirectional"))
    )
    (net (code "68") (name "Net-(U1-RO)") (class "Default")
      (node (ref "JP12") (pin "2") (pinfunction "2_2") (pintype "passive"))
      (node (ref "U1") (pin "2") (pinfunction "RO_2") (pintype "bidirectional"))
    )
    (net (code "69") (name "Net-(U1-Y)") (class "Default")
      (node (ref "J39") (pin "4") (pinfunction "4_4") (pintype "passive"))
      (node (ref "U1") (pin "5") (pinfunction "Y_5") (pintype "bidirectional"))
    )
    (net (code "70") (name "Net-(U1-Z)") (class "Default")
      (node (ref "J39") (pin "3") (pinfunction "3_3") (pintype "passive"))
      (node (ref "U1") (pin "6") (pinfunction "Z_6") (pintype "bidirectional"))
    )
    (net (code "71") (name "unconnected-(J26-Pad2)") (class "Default")
      (node (ref "J26") (pin "2") (pinfunction "2_2") (pintype "passive"))
    )
    (net (code "72") (name "unconnected-(J26-Pad3)") (class "Default")
      (node (ref "J26") (pin "3") (pinfunction "3_3") (pintype "passive"))
    )
    (net (code "73") (name "unconnected-(J26-Pad4)") (class "Default")
      (node (ref "J26") (pin "4") (pinfunction "4_4") (pintype "passive"))
    )
    (net (code "74") (name "unconnected-(J26-Pad5)") (class "Default")
      (node (ref "J26") (pin "5") (pinfunction "5_5") (pintype "passive"))
    )
  )
)
